# remoticon_v1.net
KiCad netlist of a schematic drawn in EAGLE
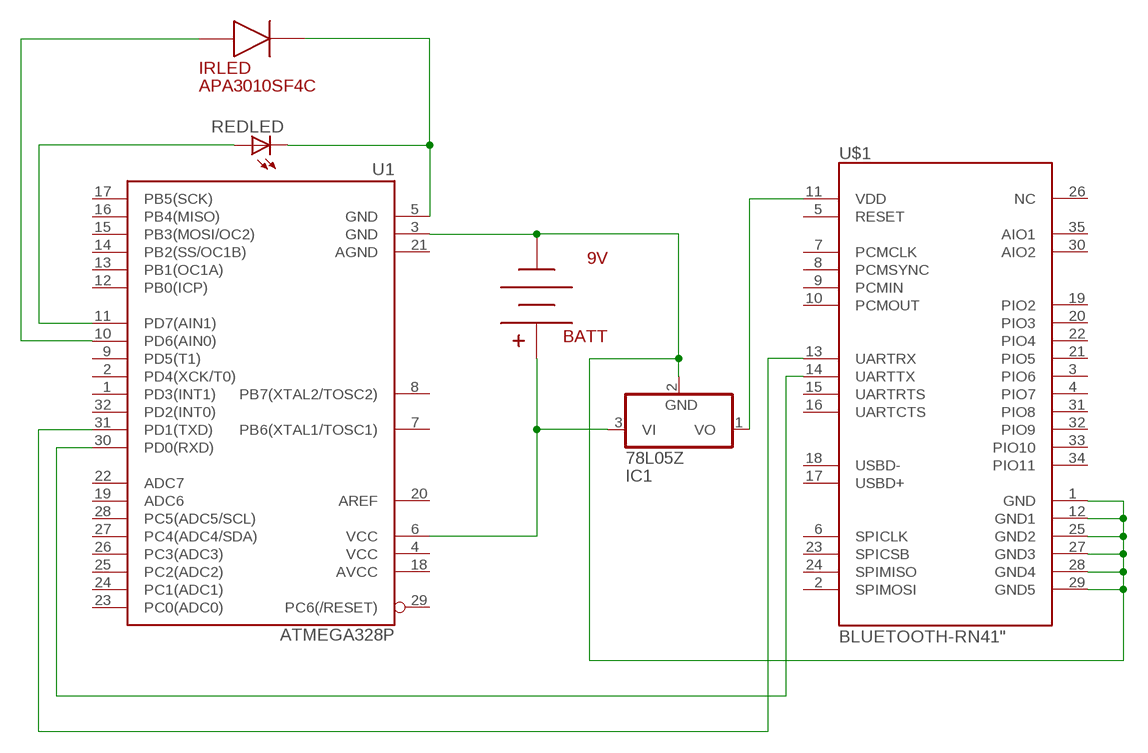
[diagram p0: schematic, sheet 1]

(export (version "E")
  (design (tool "Eeschema 10.0.6"))
  (components
    (comp (ref "BATT")
      (value "9V")
      (footprint "eagle-import:BC9VPC")
      (libsource (lib "eagle-import") (part "BC9VPC"))
    )
    (comp (ref "IC1")
      (value "78L05Z")
      (footprint "eagle-import:TO92")
      (libsource (lib "eagle-import") (part "78ZL05"))
    )
    (comp (ref "IRLED")
      (value "APA3010SF4C")
      (footprint "eagle-import:APA3010SF4C")
      (libsource (lib "eagle-import") (part "APA3010SF4C"))
    )
    (comp (ref "REDLED")
      (value "LED3MM")
      (footprint "eagle-import:LED3MM")
      (libsource (lib "eagle-import") (part "LED3MM"))
    )
    (comp (ref "U$1")
      (value "BLUETOOTH-RN41\"")
      (footprint "eagle-import:RN41")
      (libsource (lib "eagle-import") (part "BLUETOOTH-RN41{dblquote}"))
    )
    (comp (ref "U1")
      (value "ATMEGA328P")
      (footprint "eagle-import:TQFP32-08")
      (libsource (lib "eagle-import") (part "ATMEGA328_SMT"))
    )
  )
  (nets
    (net (code "1") (name "Net-(IC1-GND)") (class "Default")
      (node (ref "BATT") (pin "V-") (pinfunction "V-_V-") (pintype "bidirectional"))
      (node (ref "IC1") (pin "2") (pinfunction "GND_2") (pintype "passive"))
      (node (ref "U$1") (pin "1") (pinfunction "GND_1") (pintype "bidirectional"))
      (node (ref "U$1") (pin "12") (pinfunction "GND1_12") (pintype "bidirectional"))
      (node (ref "U$1") (pin "25") (pinfunction "GND2_25") (pintype "bidirectional"))
      (node (ref "U$1") (pin "27") (pinfunction "GND3_27") (pintype "bidirectional"))
      (node (ref "U$1") (pin "28") (pinfunction "GND4_28") (pintype "bidirectional"))
      (node (ref "U$1") (pin "29") (pinfunction "GND5_29") (pintype "bidirectional"))
      (node (ref "U1") (pin "3") (pinfunction "GND_3") (pintype "bidirectional"))
    )
    (net (code "2") (name "Net-(IC1-VI)") (class "Default")
      (node (ref "BATT") (pin "V+") (pinfunction "V+_V+") (pintype "bidirectional"))
      (node (ref "IC1") (pin "3") (pinfunction "VI_3") (pintype "input"))
      (node (ref "U1") (pin "6") (pinfunction "VCC_6") (pintype "bidirectional"))
    )
    (net (code "3") (name "Net-(IC1-VO)") (class "Default")
      (node (ref "IC1") (pin "1") (pinfunction "VO_1") (pintype "passive"))
      (node (ref "U$1") (pin "11") (pinfunction "VDD_11") (pintype "bidirectional"))
    )
    (net (code "4") (name "Net-(REDLED-C)") (class "Default")
      (node (ref "IRLED") (pin "2") (pinfunction "2_2") (pintype "bidirectional"))
      (node (ref "REDLED") (pin "K") (pinfunction "C_K") (pintype "passive"))
      (node (ref "U1") (pin "5") (pinfunction "GND_5") (pintype "bidirectional"))
    )
    (net (code "5") (name "Net-(U$1-UARTRX)") (class "Default")
      (node (ref "U$1") (pin "13") (pinfunction "UARTRX_13") (pintype "bidirectional"))
      (node (ref "U1") (pin "31") (pinfunction "PD1(TXD)_31") (pintype "bidirectional"))
    )
    (net (code "6") (name "Net-(U$1-UARTTX)") (class "Default")
      (node (ref "U$1") (pin "14") (pinfunction "UARTTX_14") (pintype "bidirectional"))
      (node (ref "U1") (pin "30") (pinfunction "PD0(RXD)_30") (pintype "bidirectional"))
    )
    (net (code "7") (name "Net-(U1-PD6(AIN0))") (class "Default")
      (node (ref "IRLED") (pin "1") (pinfunction "1_1") (pintype "bidirectional"))
      (node (ref "U1") (pin "10") (pinfunction "PD6(AIN0)_10") (pintype "bidirectional"))
    )
    (net (code "8") (name "Net-(U1-PD7(AIN1))") (class "Default")
      (node (ref "REDLED") (pin "A") (pinfunction "A_A") (pintype "passive"))
      (node (ref "U1") (pin "11") (pinfunction "PD7(AIN1)_11") (pintype "bidirectional"))
    )
    (net (code "9") (name "unconnected-(U$1-AIO1-Pad35)") (class "Default")
      (node (ref "U$1") (pin "35") (pinfunction "AIO1_35") (pintype "bidirectional"))
    )
    (net (code "10") (name "unconnected-(U$1-AIO2-Pad30)") (class "Default")
      (node (ref "U$1") (pin "30") (pinfunction "AIO2_30") (pintype "bidirectional"))
    )
    (net (code "11") (name "unconnected-(U$1-NC-Pad26)") (class "Default")
      (node (ref "U$1") (pin "26") (pinfunction "NC_26") (pintype "bidirectional"))
    )
    (net (code "12") (name "unconnected-(U$1-PCMCLK-Pad7)") (class "Default")
      (node (ref "U$1") (pin "7") (pinfunction "PCMCLK_7") (pintype "bidirectional"))
    )
    (net (code "13") (name "unconnected-(U$1-PCMIN-Pad9)") (class "Default")
      (node (ref "U$1") (pin "9") (pinfunction "PCMIN_9") (pintype "bidirectional"))
    )
    (net (code "14") (name "unconnected-(U$1-PCMOUT-Pad10)") (class "Default")
      (node (ref "U$1") (pin "10") (pinfunction "PCMOUT_10") (pintype "bidirectional"))
    )
    (net (code "15") (name "unconnected-(U$1-PCMSYNC-Pad8)") (class "Default")
      (node (ref "U$1") (pin "8") (pinfunction "PCMSYNC_8") (pintype "bidirectional"))
    )
    (net (code "16") (name "unconnected-(U$1-PIO2-Pad19)") (class "Default")
      (node (ref "U$1") (pin "19") (pinfunction "PIO2_19") (pintype "bidirectional"))
    )
    (net (code "17") (name "unconnected-(U$1-PIO3-Pad20)") (class "Default")
      (node (ref "U$1") (pin "20") (pinfunction "PIO3_20") (pintype "bidirectional"))
    )
    (net (code "18") (name "unconnected-(U$1-PIO4-Pad22)") (class "Default")
      (node (ref "U$1") (pin "22") (pinfunction "PIO4_22") (pintype "bidirectional"))
    )
    (net (code "19") (name "unconnected-(U$1-PIO5-Pad21)") (class "Default")
      (node (ref "U$1") (pin "21") (pinfunction "PIO5_21") (pintype "bidirectional"))
    )
    (net (code "20") (name "unconnected-(U$1-PIO6-Pad3)") (class "Default")
      (node (ref "U$1") (pin "3") (pinfunction "PIO6_3") (pintype "bidirectional"))
    )
    (net (code "21") (name "unconnected-(U$1-PIO7-Pad4)") (class "Default")
      (node (ref "U$1") (pin "4") (pinfunction "PIO7_4") (pintype "bidirectional"))
    )
    (net (code "22") (name "unconnected-(U$1-PIO8-Pad31)") (class "Default")
      (node (ref "U$1") (pin "31") (pinfunction "PIO8_31") (pintype "bidirectional"))
    )
    (net (code "23") (name "unconnected-(U$1-PIO9-Pad32)") (class "Default")
      (node (ref "U$1") (pin "32") (pinfunction "PIO9_32") (pintype "bidirectional"))
    )
    (net (code "24") (name "unconnected-(U$1-PIO10-Pad33)") (class "Default")
      (node (ref "U$1") (pin "33") (pinfunction "PIO10_33") (pintype "bidirectional"))
    )
    (net (code "25") (name "unconnected-(U$1-PIO11-Pad34)") (class "Default")
      (node (ref "U$1") (pin "34") (pinfunction "PIO11_34") (pintype "bidirectional"))
    )
    (net (code "26") (name "unconnected-(U$1-RESET-Pad5)") (class "Default")
      (node (ref "U$1") (pin "5") (pinfunction "RESET_5") (pintype "bidirectional"))
    )
    (net (code "27") (name "unconnected-(U$1-SPICLK-Pad6)") (class "Default")
      (node (ref "U$1") (pin "6") (pinfunction "SPICLK_6") (pintype "bidirectional"))
    )
    (net (code "28") (name "unconnected-(U$1-SPICSB-Pad23)") (class "Default")
      (node (ref "U$1") (pin "23") (pinfunction "SPICSB_23") (pintype "bidirectional"))
    )
    (net (code "29") (name "unconnected-(U$1-SPIMISO-Pad24)") (class "Default")
      (node (ref "U$1") (pin "24") (pinfunction "SPIMISO_24") (pintype "bidirectional"))
    )
    (net (code "30") (name "unconnected-(U$1-SPIMOSI-Pad2)") (class "Default")
      (node (ref "U$1") (pin "2") (pinfunction "SPIMOSI_2") (pintype "bidirectional"))
    )
    (net (code "31") (name "unconnected-(U$1-UARTCTS-Pad16)") (class "Default")
      (node (ref "U$1") (pin "16") (pinfunction "UARTCTS_16") (pintype "bidirectional"))
    )
    (net (code "32") (name "unconnected-(U$1-UARTRTS-Pad15)") (class "Default")
      (node (ref "U$1") (pin "15") (pinfunction "UARTRTS_15") (pintype "bidirectional"))
    )
    (net (code "33") (name "unconnected-(U$1-USBD+-Pad17)") (class "Default")
      (node (ref "U$1") (pin "17") (pinfunction "USBD+_17") (pintype "bidirectional"))
    )
    (net (code "34") (name "unconnected-(U$1-USBD--Pad18)") (class "Default")
      (node (ref "U$1") (pin "18") (pinfunction "USBD-_18") (pintype "bidirectional"))
    )
    (net (code "35") (name "unconnected-(U1-ADC6-Pad19)") (class "Default")
      (node (ref "U1") (pin "19") (pinfunction "ADC6_19") (pintype "bidirectional"))
    )
    (net (code "36") (name "unconnected-(U1-ADC7-Pad22)") (class "Default")
      (node (ref "U1") (pin "22") (pinfunction "ADC7_22") (pintype "bidirectional"))
    )
    (net (code "37") (name "unconnected-(U1-AGND-Pad21)") (class "Default")
      (node (ref "U1") (pin "21") (pinfunction "AGND_21") (pintype "bidirectional"))
    )
    (net (code "38") (name "unconnected-(U1-AREF-Pad20)") (class "Default")
      (node (ref "U1") (pin "20") (pinfunction "AREF_20") (pintype "bidirectional"))
    )
    (net (code "39") (name "unconnected-(U1-AVCC-Pad18)") (class "Default")
      (node (ref "U1") (pin "18") (pinfunction "AVCC_18") (pintype "bidirectional"))
    )
    (net (code "40") (name "unconnected-(U1-PB0(ICP)-Pad12)") (class "Default")
      (node (ref "U1") (pin "12") (pinfunction "PB0(ICP)_12") (pintype "bidirectional"))
    )
    (net (code "41") (name "unconnected-(U1-PB1(OC1A)-Pad13)") (class "Default")
      (node (ref "U1") (pin "13") (pinfunction "PB1(OC1A)_13") (pintype "bidirectional"))
    )
    (net (code "42") (name "unconnected-(U1-PB2(SS{slash}OC1B)-Pad14)") (class "Default")
      (node (ref "U1") (pin "14") (pinfunction "PB2(SS/OC1B)_14") (pintype "bidirectional"))
    )
    (net (code "43") (name "unconnected-(U1-PB3(MOSI{slash}OC2)-Pad15)") (class "Default")
      (node (ref "U1") (pin "15") (pinfunction "PB3(MOSI/OC2)_15") (pintype "bidirectional"))
    )
    (net (code "44") (name "unconnected-(U1-PB4(MISO)-Pad16)") (class "Default")
      (node (ref "U1") (pin "16") (pinfunction "PB4(MISO)_16") (pintype "bidirectional"))
    )
    (net (code "45") (name "unconnected-(U1-PB5(SCK)-Pad17)") (class "Default")
      (node (ref "U1") (pin "17") (pinfunction "PB5(SCK)_17") (pintype "bidirectional"))
    )
    (net (code "46") (name "unconnected-(U1-PB6(XTAL1{slash}TOSC1)-Pad7)") (class "Default")
      (node (ref "U1") (pin "7") (pinfunction "PB6(XTAL1/TOSC1)_7") (pintype "bidirectional"))
    )
    (net (code "47") (name "unconnected-(U1-PB7(XTAL2{slash}TOSC2)-Pad8)") (class "Default")
      (node (ref "U1") (pin "8") (pinfunction "PB7(XTAL2/TOSC2)_8") (pintype "bidirectional"))
    )
    (net (code "48") (name "unconnected-(U1-PC0(ADC0)-Pad23)") (class "Default")
      (node (ref "U1") (pin "23") (pinfunction "PC0(ADC0)_23") (pintype "bidirectional"))
    )
    (net (code "49") (name "unconnected-(U1-PC1(ADC1)-Pad24)") (class "Default")
      (node (ref "U1") (pin "24") (pinfunction "PC1(ADC1)_24") (pintype "bidirectional"))
    )
    (net (code "50") (name "unconnected-(U1-PC2(ADC2)-Pad25)") (class "Default")
      (node (ref "U1") (pin "25") (pinfunction "PC2(ADC2)_25") (pintype "bidirectional"))
    )
    (net (code "51") (name "unconnected-(U1-PC3(ADC3)-Pad26)") (class "Default")
      (node (ref "U1") (pin "26") (pinfunction "PC3(ADC3)_26") (pintype "bidirectional"))
    )
    (net (code "52") (name "unconnected-(U1-PC4(ADC4{slash}SDA)-Pad27)") (class "Default")
      (node (ref "U1") (pin "27") (pinfunction "PC4(ADC4/SDA)_27") (pintype "bidirectional"))
    )
    (net (code "53") (name "unconnected-(U1-PC5(ADC5{slash}SCL)-Pad28)") (class "Default")
      (node (ref "U1") (pin "28") (pinfunction "PC5(ADC5/SCL)_28") (pintype "bidirectional"))
    )
    (net (code "54") (name "unconnected-(U1-PC6({slash}RESET)-Pad29)") (class "Default")
      (node (ref "U1") (pin "29") (pinfunction "PC6(/RESET)_29") (pintype "bidirectional"))
    )
    (net (code "55") (name "unconnected-(U1-PD2(INT0)-Pad32)") (class "Default")
      (node (ref "U1") (pin "32") (pinfunction "PD2(INT0)_32") (pintype "bidirectional"))
    )
    (net (code "56") (name "unconnected-(U1-PD3(INT1)-Pad1)") (class "Default")
      (node (ref "U1") (pin "1") (pinfunction "PD3(INT1)_1") (pintype "bidirectional"))
    )
    (net (code "57") (name "unconnected-(U1-PD4(XCK{slash}T0)-Pad2)") (class "Default")
      (node (ref "U1") (pin "2") (pinfunction "PD4(XCK/T0)_2") (pintype "bidirectional"))
    )
    (net (code "58") (name "unconnected-(U1-PD5(T1)-Pad9)") (class "Default")
      (node (ref "U1") (pin "9") (pinfunction "PD5(T1)_9") (pintype "bidirectional"))
    )
    (net (code "59") (name "unconnected-(U1-VCC-Pad4)") (class "Default")
      (node (ref "U1") (pin "4") (pinfunction "VCC_4") (pintype "bidirectional"))
    )
  )
)
